# encore_Main_Board.net
KiCad netlist of a schematic drawn in EAGLE
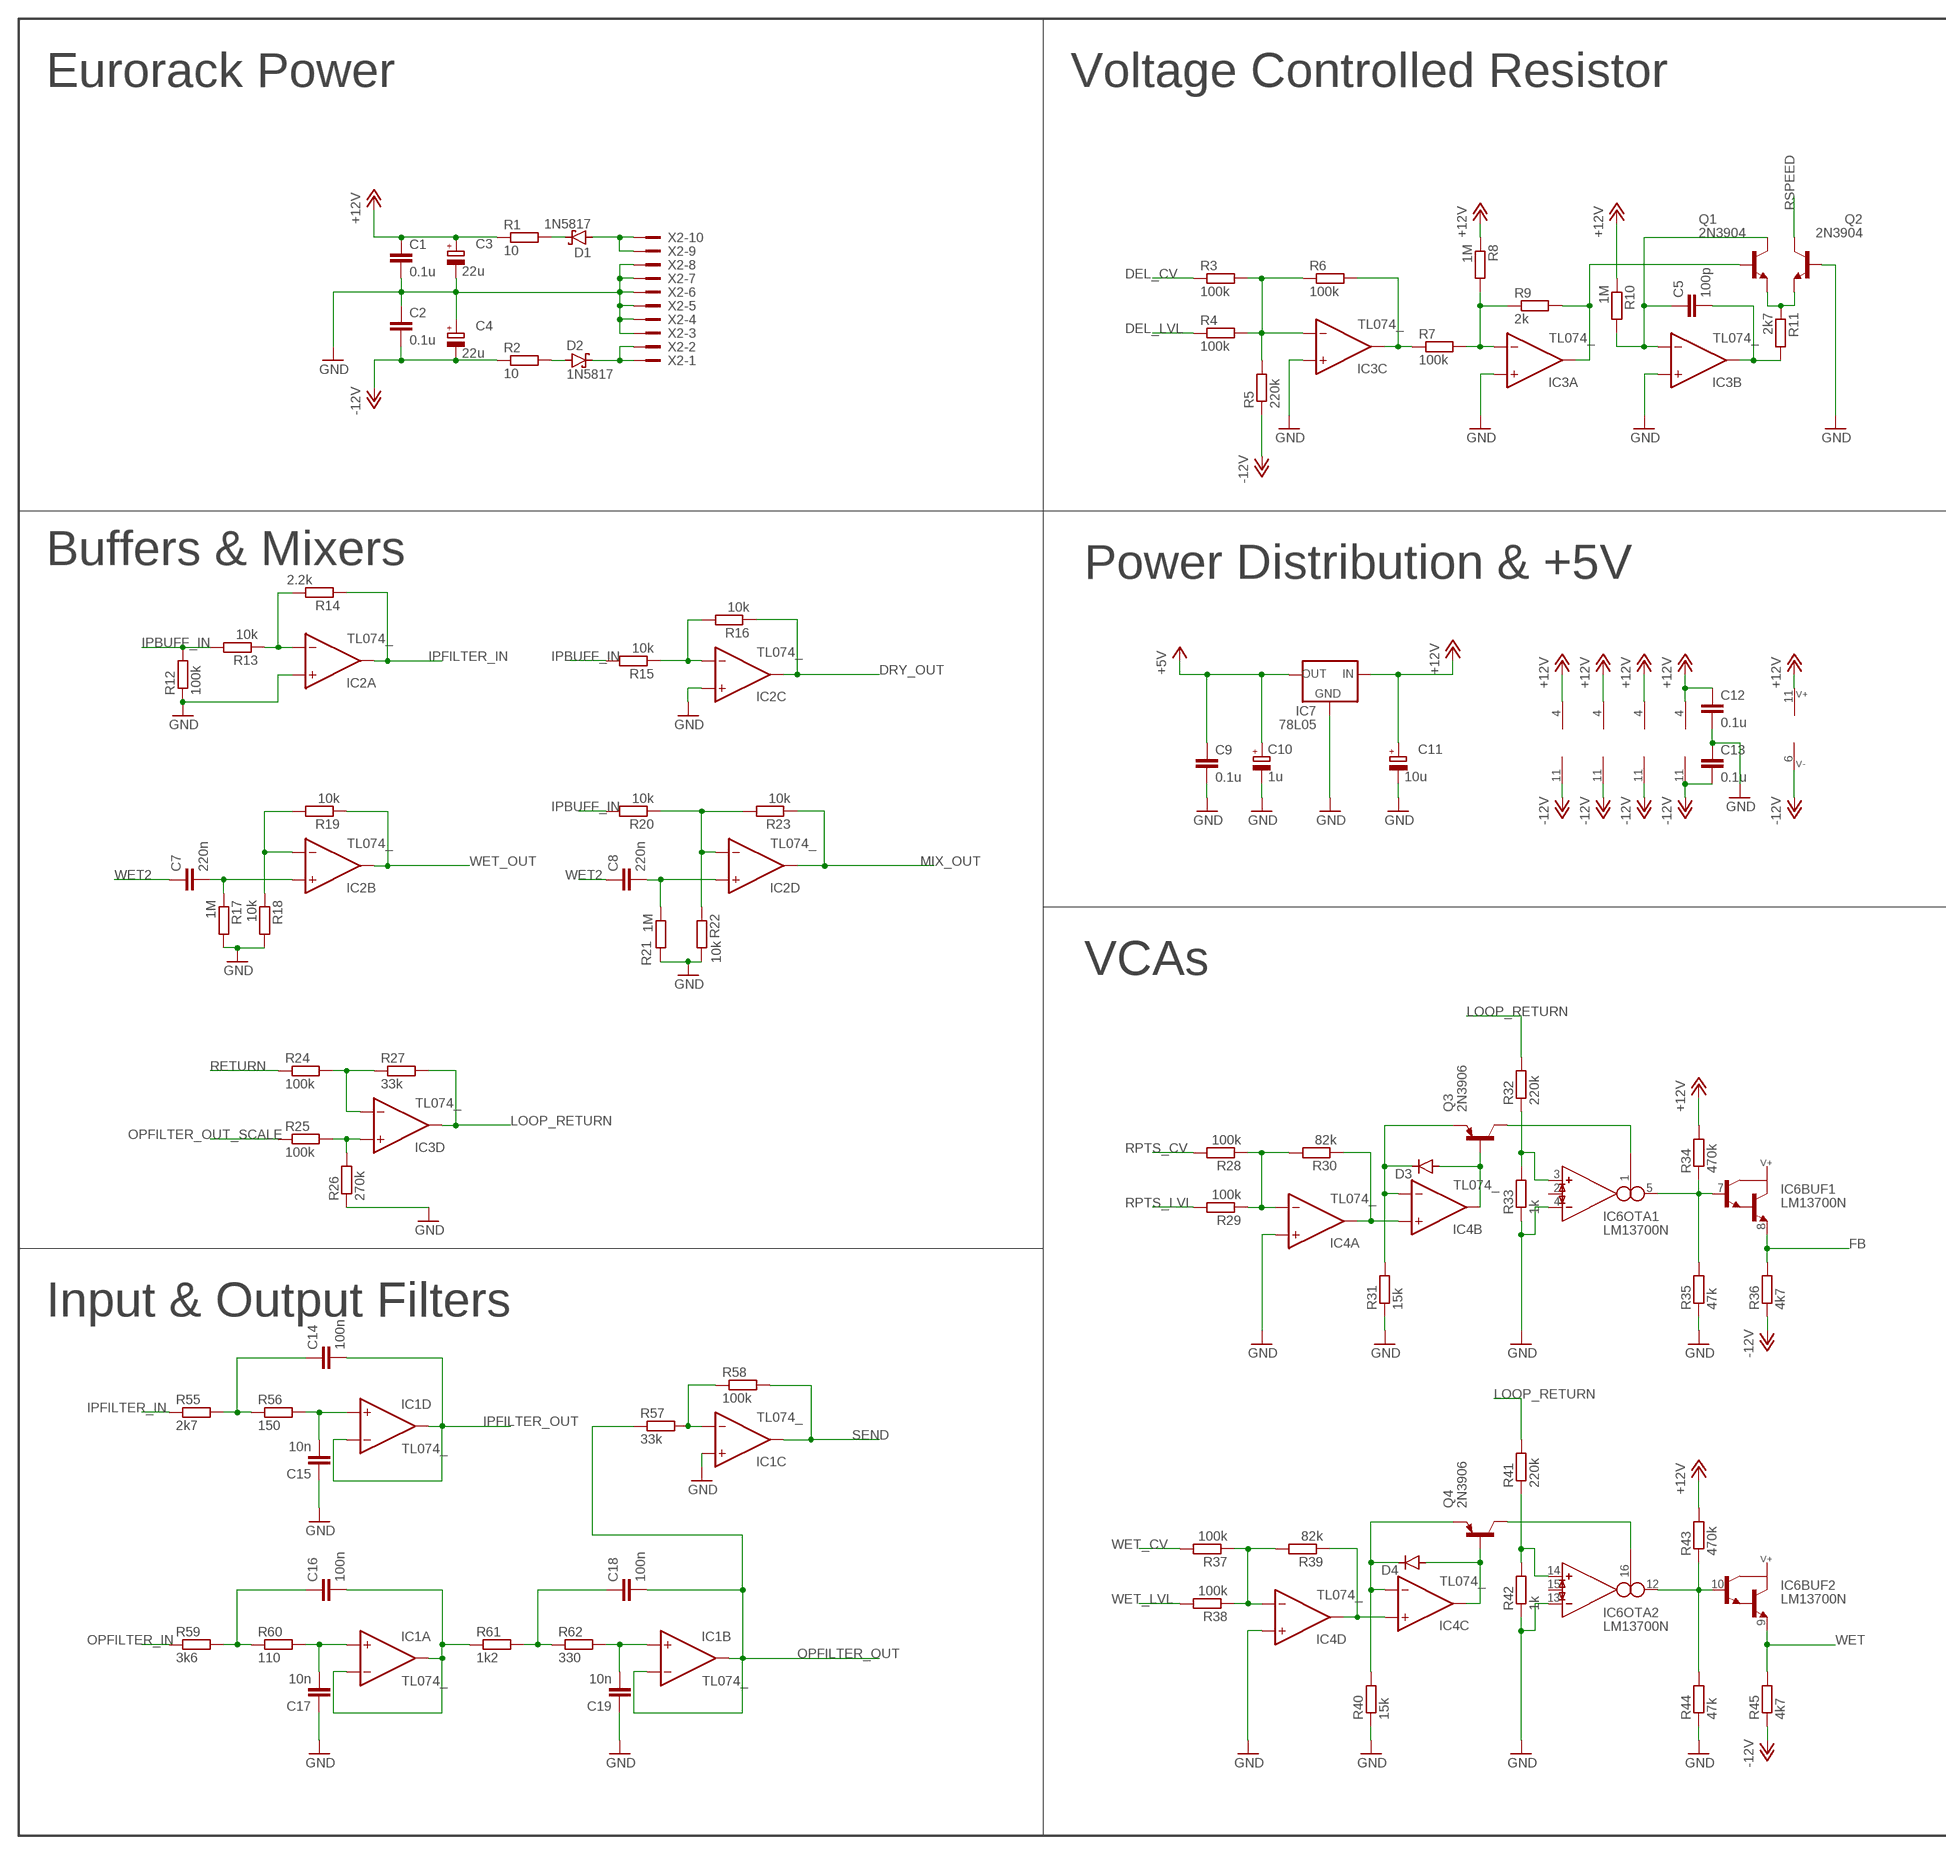
[diagram p0: schematic, sheet 1, part 1 of 2]
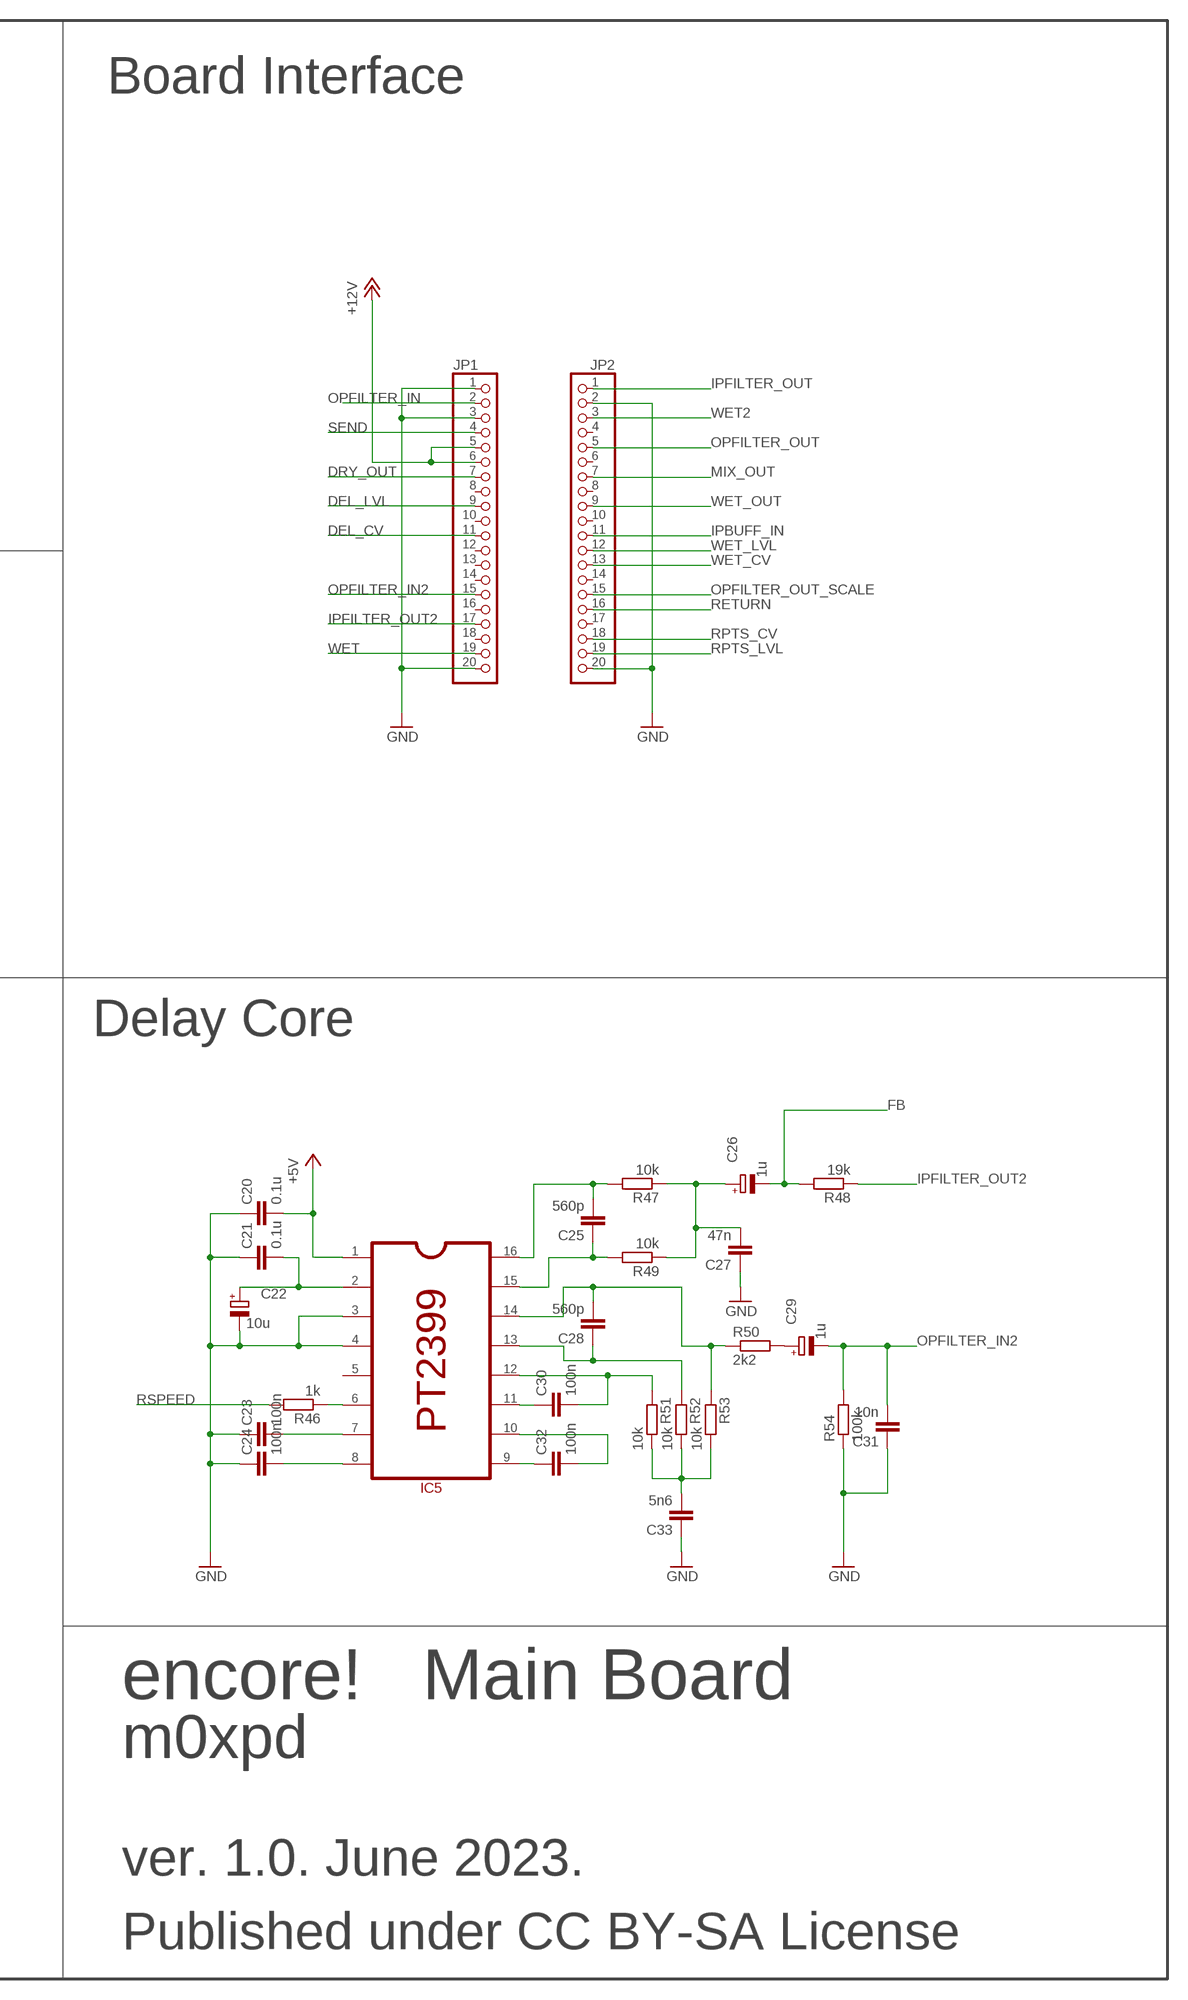
[diagram p1: schematic, sheet 1, part 2 of 2]

(export (version "E")
  (design (tool "Eeschema 10.0.6"))
  (components
    (comp (ref "C1")
      (value "0.1u")
      (footprint "eagle-import:C050-025X075")
      (libsource (lib "eagle-import") (part "C-EU050-025X075"))
    )
    (comp (ref "C2")
      (value "0.1u")
      (footprint "eagle-import:C050-025X075")
      (libsource (lib "eagle-import") (part "C-EU050-025X075"))
    )
    (comp (ref "C3")
      (value "22u")
      (footprint "eagle-import:E2,5-5")
      (libsource (lib "eagle-import") (part "CPOL-EUE2.5-5"))
    )
    (comp (ref "C4")
      (value "22u")
      (footprint "eagle-import:E2,5-5")
      (libsource (lib "eagle-import") (part "CPOL-EUE2.5-5"))
    )
    (comp (ref "C5")
      (value "100p")
      (footprint "eagle-import:C025-025X050")
      (libsource (lib "eagle-import") (part "C-EU025-025X050"))
    )
    (comp (ref "C7")
      (value "220n")
      (footprint "eagle-import:C050-024X044")
      (libsource (lib "eagle-import") (part "C-EU050-024X044"))
    )
    (comp (ref "C8")
      (value "220n")
      (footprint "eagle-import:C050-024X044")
      (libsource (lib "eagle-import") (part "C-EU050-024X044"))
    )
    (comp (ref "C9")
      (value "0.1u")
      (footprint "eagle-import:C050-025X075")
      (libsource (lib "eagle-import") (part "C-EU050-025X075"))
    )
    (comp (ref "C10")
      (value "1u")
      (footprint "eagle-import:E2,5-5")
      (libsource (lib "eagle-import") (part "CPOL-EUE2.5-5"))
    )
    (comp (ref "C11")
      (value "10u")
      (footprint "eagle-import:E2,5-5")
      (libsource (lib "eagle-import") (part "CPOL-EUE2.5-5"))
    )
    (comp (ref "C12")
      (value "0.1u")
      (footprint "eagle-import:C050-025X075")
      (libsource (lib "eagle-import") (part "C-EU050-025X075"))
    )
    (comp (ref "C13")
      (value "0.1u")
      (footprint "eagle-import:C050-025X075")
      (libsource (lib "eagle-import") (part "C-EU050-025X075"))
    )
    (comp (ref "C14")
      (value "100n")
      (footprint "eagle-import:C025-025X050")
      (libsource (lib "eagle-import") (part "C-EU025-025X050"))
    )
    (comp (ref "C15")
      (value "10n")
      (footprint "eagle-import:C025-025X050")
      (libsource (lib "eagle-import") (part "C-EU025-025X050"))
    )
    (comp (ref "C16")
      (value "100n")
      (footprint "eagle-import:C025-025X050")
      (libsource (lib "eagle-import") (part "C-EU025-025X050"))
    )
    (comp (ref "C17")
      (value "10n")
      (footprint "eagle-import:C025-025X050")
      (libsource (lib "eagle-import") (part "C-EU025-025X050"))
    )
    (comp (ref "C18")
      (value "100n")
      (footprint "eagle-import:C025-025X050")
      (libsource (lib "eagle-import") (part "C-EU025-025X050"))
    )
    (comp (ref "C19")
      (value "10n")
      (footprint "eagle-import:C025-025X050")
      (libsource (lib "eagle-import") (part "C-EU025-025X050"))
    )
    (comp (ref "C20")
      (value "0.1u")
      (footprint "eagle-import:C050-025X075")
      (libsource (lib "eagle-import") (part "C-EU050-025X075"))
    )
    (comp (ref "C21")
      (value "0.1u")
      (footprint "eagle-import:C050-025X075")
      (libsource (lib "eagle-import") (part "C-EU050-025X075"))
    )
    (comp (ref "C22")
      (value "10u")
      (footprint "eagle-import:E2,5-5")
      (libsource (lib "eagle-import") (part "CPOL-EUE2.5-5"))
    )
    (comp (ref "C23")
      (value "100n")
      (footprint "eagle-import:C050-025X075")
      (libsource (lib "eagle-import") (part "C-EU050-025X075"))
    )
    (comp (ref "C24")
      (value "100n")
      (footprint "eagle-import:C050-025X075")
      (libsource (lib "eagle-import") (part "C-EU050-025X075"))
    )
    (comp (ref "C25")
      (value "560p")
      (footprint "eagle-import:C025-025X050")
      (libsource (lib "eagle-import") (part "C-EU025-025X050"))
    )
    (comp (ref "C26")
      (value "1u")
      (footprint "eagle-import:E2,5-5")
      (libsource (lib "eagle-import") (part "CPOL-EUE2.5-5"))
    )
    (comp (ref "C27")
      (value "47n")
      (footprint "eagle-import:C050-025X075")
      (libsource (lib "eagle-import") (part "C-EU050-025X075"))
    )
    (comp (ref "C28")
      (value "560p")
      (footprint "eagle-import:C025-025X050")
      (libsource (lib "eagle-import") (part "C-EU025-025X050"))
    )
    (comp (ref "C29")
      (value "1u")
      (footprint "eagle-import:E2,5-5")
      (libsource (lib "eagle-import") (part "CPOL-EUE2.5-5"))
    )
    (comp (ref "C30")
      (value "100n")
      (footprint "eagle-import:C050-025X075")
      (libsource (lib "eagle-import") (part "C-EU050-025X075"))
    )
    (comp (ref "C31")
      (value "10n")
      (footprint "eagle-import:C025-025X050")
      (libsource (lib "eagle-import") (part "C-EU025-025X050"))
    )
    (comp (ref "C32")
      (value "100n")
      (footprint "eagle-import:C050-025X075")
      (libsource (lib "eagle-import") (part "C-EU050-025X075"))
    )
    (comp (ref "C33")
      (value "5n6")
      (footprint "eagle-import:C050-025X075")
      (libsource (lib "eagle-import") (part "C-EU050-025X075"))
    )
    (comp (ref "D1")
      (value "1N5817")
      (footprint "eagle-import:DO35-7")
      (libsource (lib "eagle-import") (part "SCHOTTKY-DIODEDO35-7"))
    )
    (comp (ref "D2")
      (value "1N5817")
      (footprint "eagle-import:DO35-7")
      (libsource (lib "eagle-import") (part "SCHOTTKY-DIODEDO35-7"))
    )
    (comp (ref "D3")
      (value "1N4148DO35-7")
      (footprint "eagle-import:DO35-7")
      (libsource (lib "eagle-import") (part "1N4148DO35-7"))
    )
    (comp (ref "D4")
      (value "1N4148DO35-7")
      (footprint "eagle-import:DO35-7")
      (libsource (lib "eagle-import") (part "1N4148DO35-7"))
    )
    (comp (ref "IC1")
      (value "TL074_")
      (footprint "eagle-import:DIL14")
      (libsource (lib "eagle-import") (part "TL074_"))
    )
    (comp (ref "IC2")
      (value "TL074_")
      (footprint "eagle-import:DIL14")
      (libsource (lib "eagle-import") (part "TL074_"))
    )
    (comp (ref "IC3")
      (value "TL074_")
      (footprint "eagle-import:DIL14")
      (libsource (lib "eagle-import") (part "TL074_"))
    )
    (comp (ref "IC4")
      (value "TL074_")
      (footprint "eagle-import:DIL14")
      (libsource (lib "eagle-import") (part "TL074_"))
    )
    (comp (ref "IC5")
      (value "PT2399")
      (footprint "eagle-import:DIP-16")
      (libsource (lib "eagle-import") (part "PT2399"))
    )
    (comp (ref "IC6")
      (value "LM13700N")
      (footprint "eagle-import:DIL16")
      (libsource (lib "eagle-import") (part "LM13700N"))
    )
    (comp (ref "IC7")
      (value "78L05")
      (footprint "eagle-import:78LXX")
      (libsource (lib "eagle-import") (part "78LXX"))
    )
    (comp (ref "JP1")
      (value "PINHD-1X20")
      (footprint "eagle-import:1X20")
      (libsource (lib "eagle-import") (part "PINHD-1X20"))
    )
    (comp (ref "JP2")
      (value "PINHD-1X20")
      (footprint "eagle-import:1X20")
      (libsource (lib "eagle-import") (part "PINHD-1X20"))
    )
    (comp (ref "Q1")
      (value "2N3904")
      (footprint "eagle-import:TO92")
      (libsource (lib "eagle-import") (part "2N3904"))
    )
    (comp (ref "Q2")
      (value "2N3904")
      (footprint "eagle-import:TO92")
      (libsource (lib "eagle-import") (part "2N3904"))
    )
    (comp (ref "Q3")
      (value "2N3906")
      (footprint "eagle-import:TO92")
      (libsource (lib "eagle-import") (part "2N3906"))
    )
    (comp (ref "Q4")
      (value "2N3906")
      (footprint "eagle-import:TO92")
      (libsource (lib "eagle-import") (part "2N3906"))
    )
    (comp (ref "R1")
      (value "10")
      (footprint "eagle-import:0204_7")
      (libsource (lib "eagle-import") (part "R-EU_0204/7"))
    )
    (comp (ref "R2")
      (value "10")
      (footprint "eagle-import:0204_7")
      (libsource (lib "eagle-import") (part "R-EU_0204/7"))
    )
    (comp (ref "R3")
      (value "100k")
      (footprint "eagle-import:0204_7")
      (libsource (lib "eagle-import") (part "R-EU_0204/7"))
    )
    (comp (ref "R4")
      (value "100k")
      (footprint "eagle-import:0204_7")
      (libsource (lib "eagle-import") (part "R-EU_0204/7"))
    )
    (comp (ref "R5")
      (value "220k")
      (footprint "eagle-import:0204_7")
      (libsource (lib "eagle-import") (part "R-EU_0204/7"))
    )
    (comp (ref "R6")
      (value "100k")
      (footprint "eagle-import:0204_7")
      (libsource (lib "eagle-import") (part "R-EU_0204/7"))
    )
    (comp (ref "R7")
      (value "100k")
      (footprint "eagle-import:0204_7")
      (libsource (lib "eagle-import") (part "R-EU_0204/7"))
    )
    (comp (ref "R8")
      (value "1M")
      (footprint "eagle-import:0204_7")
      (libsource (lib "eagle-import") (part "R-EU_0204/7"))
    )
    (comp (ref "R9")
      (value "2k")
      (footprint "eagle-import:0204_7")
      (libsource (lib "eagle-import") (part "R-EU_0204/7"))
    )
    (comp (ref "R10")
      (value "1M")
      (footprint "eagle-import:0204_7")
      (libsource (lib "eagle-import") (part "R-EU_0204/7"))
    )
    (comp (ref "R11")
      (value "2k7")
      (footprint "eagle-import:0204_7")
      (libsource (lib "eagle-import") (part "R-EU_0204/7"))
    )
    (comp (ref "R12")
      (value "100k")
      (footprint "eagle-import:0204_7")
      (libsource (lib "eagle-import") (part "R-EU_0204/7"))
    )
    (comp (ref "R13")
      (value "10k")
      (footprint "eagle-import:0204_7")
      (libsource (lib "eagle-import") (part "R-EU_0204/7"))
    )
    (comp (ref "R14")
      (value "2.2k")
      (footprint "eagle-import:0204_7")
      (libsource (lib "eagle-import") (part "R-EU_0204/7"))
    )
    (comp (ref "R15")
      (value "10k")
      (footprint "eagle-import:0204_7")
      (libsource (lib "eagle-import") (part "R-EU_0204/7"))
    )
    (comp (ref "R16")
      (value "10k")
      (footprint "eagle-import:0204_7")
      (libsource (lib "eagle-import") (part "R-EU_0204/7"))
    )
    (comp (ref "R17")
      (value "1M")
      (footprint "eagle-import:0204_7")
      (libsource (lib "eagle-import") (part "R-EU_0204/7"))
    )
    (comp (ref "R18")
      (value "10k")
      (footprint "eagle-import:0204_7")
      (libsource (lib "eagle-import") (part "R-EU_0204/7"))
    )
    (comp (ref "R19")
      (value "10k")
      (footprint "eagle-import:0204_7")
      (libsource (lib "eagle-import") (part "R-EU_0204/7"))
    )
    (comp (ref "R20")
      (value "10k")
      (footprint "eagle-import:0204_7")
      (libsource (lib "eagle-import") (part "R-EU_0204/7"))
    )
    (comp (ref "R21")
      (value "1M")
      (footprint "eagle-import:0204_7")
      (libsource (lib "eagle-import") (part "R-EU_0204/7"))
    )
    (comp (ref "R22")
      (value "10k")
      (footprint "eagle-import:0204_7")
      (libsource (lib "eagle-import") (part "R-EU_0204/7"))
    )
    (comp (ref "R23")
      (value "10k")
      (footprint "eagle-import:0204_7")
      (libsource (lib "eagle-import") (part "R-EU_0204/7"))
    )
    (comp (ref "R24")
      (value "100k")
      (footprint "eagle-import:0204_7")
      (libsource (lib "eagle-import") (part "R-EU_0204/7"))
    )
    (comp (ref "R25")
      (value "100k")
      (footprint "eagle-import:0204_7")
      (libsource (lib "eagle-import") (part "R-EU_0204/7"))
    )
    (comp (ref "R26")
      (value "270k")
      (footprint "eagle-import:0204_7")
      (libsource (lib "eagle-import") (part "R-EU_0204/7"))
    )
    (comp (ref "R27")
      (value "33k")
      (footprint "eagle-import:0204_7")
      (libsource (lib "eagle-import") (part "R-EU_0204/7"))
    )
    (comp (ref "R28")
      (value "100k")
      (footprint "eagle-import:0204_7")
      (libsource (lib "eagle-import") (part "R-EU_0204/7"))
    )
    (comp (ref "R29")
      (value "100k")
      (footprint "eagle-import:0204_7")
      (libsource (lib "eagle-import") (part "R-EU_0204/7"))
    )
    (comp (ref "R30")
      (value "82k")
      (footprint "eagle-import:0204_7")
      (libsource (lib "eagle-import") (part "R-EU_0204/7"))
    )
    (comp (ref "R31")
      (value "15k")
      (footprint "eagle-import:0204_7")
      (libsource (lib "eagle-import") (part "R-EU_0204/7"))
    )
    (comp (ref "R32")
      (value "220k")
      (footprint "eagle-import:0204_7")
      (libsource (lib "eagle-import") (part "R-EU_0204/7"))
    )
    (comp (ref "R33")
      (value "1k")
      (footprint "eagle-import:0204_7")
      (libsource (lib "eagle-import") (part "R-EU_0204/7"))
    )
    (comp (ref "R34")
      (value "470k")
      (footprint "eagle-import:0204_7")
      (libsource (lib "eagle-import") (part "R-EU_0204/7"))
    )
    (comp (ref "R35")
      (value "47k")
      (footprint "eagle-import:0204_7")
      (libsource (lib "eagle-import") (part "R-EU_0204/7"))
    )
    (comp (ref "R36")
      (value "4k7")
      (footprint "eagle-import:0204_7")
      (libsource (lib "eagle-import") (part "R-EU_0204/7"))
    )
    (comp (ref "R37")
      (value "100k")
      (footprint "eagle-import:0204_7")
      (libsource (lib "eagle-import") (part "R-EU_0204/7"))
    )
    (comp (ref "R38")
      (value "100k")
      (footprint "eagle-import:0204_7")
      (libsource (lib "eagle-import") (part "R-EU_0204/7"))
    )
    (comp (ref "R39")
      (value "82k")
      (footprint "eagle-import:0204_7")
      (libsource (lib "eagle-import") (part "R-EU_0204/7"))
    )
    (comp (ref "R40")
      (value "15k")
      (footprint "eagle-import:0204_7")
      (libsource (lib "eagle-import") (part "R-EU_0204/7"))
    )
    (comp (ref "R41")
      (value "220k")
      (footprint "eagle-import:0204_7")
      (libsource (lib "eagle-import") (part "R-EU_0204/7"))
    )
    (comp (ref "R42")
      (value "1k")
      (footprint "eagle-import:0204_7")
      (libsource (lib "eagle-import") (part "R-EU_0204/7"))
    )
    (comp (ref "R43")
      (value "470k")
      (footprint "eagle-import:0204_7")
      (libsource (lib "eagle-import") (part "R-EU_0204/7"))
    )
    (comp (ref "R44")
      (value "47k")
      (footprint "eagle-import:0204_7")
      (libsource (lib "eagle-import") (part "R-EU_0204/7"))
    )
    (comp (ref "R45")
      (value "4k7")
      (footprint "eagle-import:0204_7")
      (libsource (lib "eagle-import") (part "R-EU_0204/7"))
    )
    (comp (ref "R46")
      (value "1k")
      (footprint "eagle-import:0204_7")
      (libsource (lib "eagle-import") (part "R-EU_0204/7"))
    )
    (comp (ref "R47")
      (value "10k")
      (footprint "eagle-import:0204_7")
      (libsource (lib "eagle-import") (part "R-EU_0204/7"))
    )
    (comp (ref "R48")
      (value "19k")
      (footprint "eagle-import:0204_7")
      (libsource (lib "eagle-import") (part "R-EU_0204/7"))
    )
    (comp (ref "R49")
      (value "10k")
      (footprint "eagle-import:0204_7")
      (libsource (lib "eagle-import") (part "R-EU_0204/7"))
    )
    (comp (ref "R50")
      (value "2k2")
      (footprint "eagle-import:0204_7")
      (libsource (lib "eagle-import") (part "R-EU_0204/7"))
    )
    (comp (ref "R51")
      (value "10k")
      (footprint "eagle-import:0204_7")
      (libsource (lib "eagle-import") (part "R-EU_0204/7"))
    )
    (comp (ref "R52")
      (value "10k")
      (footprint "eagle-import:0204_7")
      (libsource (lib "eagle-import") (part "R-EU_0204/7"))
    )
    (comp (ref "R53")
      (value "10k")
      (footprint "eagle-import:0204_7")
      (libsource (lib "eagle-import") (part "R-EU_0204/7"))
    )
    (comp (ref "R54")
      (value "100k")
      (footprint "eagle-import:0204_7")
      (libsource (lib "eagle-import") (part "R-EU_0204/7"))
    )
    (comp (ref "R55")
      (value "2k7")
      (footprint "eagle-import:0204_7")
      (libsource (lib "eagle-import") (part "R-EU_0204/7"))
    )
    (comp (ref "R56")
      (value "150")
      (footprint "eagle-import:0204_7")
      (libsource (lib "eagle-import") (part "R-EU_0204/7"))
    )
    (comp (ref "R57")
      (value "33k")
      (footprint "eagle-import:0204_7")
      (libsource (lib "eagle-import") (part "R-EU_0204/7"))
    )
    (comp (ref "R58")
      (value "100k")
      (footprint "eagle-import:0204_7")
      (libsource (lib "eagle-import") (part "R-EU_0204/7"))
    )
    (comp (ref "R59")
      (value "3k6")
      (footprint "eagle-import:0204_7")
      (libsource (lib "eagle-import") (part "R-EU_0204/7"))
    )
    (comp (ref "R60")
      (value "110")
      (footprint "eagle-import:0204_7")
      (libsource (lib "eagle-import") (part "R-EU_0204/7"))
    )
    (comp (ref "R61")
      (value "1k2")
      (footprint "eagle-import:0204_7")
      (libsource (lib "eagle-import") (part "R-EU_0204/7"))
    )
    (comp (ref "R62")
      (value "330")
      (footprint "eagle-import:0204_7")
      (libsource (lib "eagle-import") (part "R-EU_0204/7"))
    )
    (comp (ref "X2")
      (value "2510-")
      (footprint "eagle-import:PAK100_2500-10")
      (fields (field (name "MF") "3M") (field (name "MPN") "2510-6002UB"))
      (libsource (lib "eagle-import") (part "2510-"))
    )
  )
  (nets
    (net (code "1") (name "+5V") (class "Default")
      (node (ref "C10") (pin "+") (pinfunction "+_+") (pintype "passive"))
      (node (ref "C20") (pin "2") (pinfunction "2_2") (pintype "passive"))
      (node (ref "C9") (pin "1") (pinfunction "1_1") (pintype "passive"))
      (node (ref "IC5") (pin "1") (pinfunction "1_1") (pintype "bidirectional"))
      (node (ref "IC7") (pin "OUT") (pinfunction "OUT_OUT") (pintype "passive"))
    )
    (net (code "2") (name "+12V") (class "Default")
      (node (ref "C1") (pin "1") (pinfunction "1_1") (pintype "passive"))
      (node (ref "C11") (pin "+") (pinfunction "+_+") (pintype "passive"))
      (node (ref "C12") (pin "1") (pinfunction "1_1") (pintype "passive"))
      (node (ref "C3") (pin "+") (pinfunction "+_+") (pintype "passive"))
      (node (ref "IC1") (pin "4") (pinfunction "V+_4") (pintype "power_in"))
      (node (ref "IC2") (pin "4") (pinfunction "V+_4") (pintype "power_in"))
      (node (ref "IC3") (pin "4") (pinfunction "V+_4") (pintype "power_in"))
      (node (ref "IC4") (pin "4") (pinfunction "V+_4") (pintype "power_in"))
      (node (ref "IC6") (pin "11") (pinfunction "V+_11") (pintype "power_in"))
      (node (ref "IC7") (pin "IN") (pinfunction "IN_IN") (pintype "input"))
      (node (ref "JP1") (pin "5") (pinfunction "5_5") (pintype "passive"))
      (node (ref "JP1") (pin "6") (pinfunction "6_6") (pintype "passive"))
      (node (ref "R1") (pin "1") (pinfunction "1_1") (pintype "passive"))
      (node (ref "R10") (pin "1") (pinfunction "1_1") (pintype "passive"))
      (node (ref "R34") (pin "2") (pinfunction "2_2") (pintype "passive"))
      (node (ref "R43") (pin "2") (pinfunction "2_2") (pintype "passive"))
      (node (ref "R8") (pin "1") (pinfunction "1_1") (pintype "passive"))
    )
    (net (code "3") (name "-12V") (class "Default")
      (node (ref "C13") (pin "2") (pinfunction "2_2") (pintype "passive"))
      (node (ref "C2") (pin "2") (pinfunction "2_2") (pintype "passive"))
      (node (ref "C4") (pin "-") (pinfunction "-_-") (pintype "passive"))
      (node (ref "IC1") (pin "11") (pinfunction "V-_11") (pintype "power_in"))
      (node (ref "IC2") (pin "11") (pinfunction "V-_11") (pintype "power_in"))
      (node (ref "IC3") (pin "11") (pinfunction "V-_11") (pintype "power_in"))
      (node (ref "IC4") (pin "11") (pinfunction "V-_11") (pintype "power_in"))
      (node (ref "IC6") (pin "6") (pinfunction "V-_6") (pintype "power_in"))
      (node (ref "R2") (pin "1") (pinfunction "1_1") (pintype "passive"))
      (node (ref "R36") (pin "1") (pinfunction "1_1") (pintype "passive"))
      (node (ref "R45") (pin "1") (pinfunction "1_1") (pintype "passive"))
      (node (ref "R5") (pin "1") (pinfunction "1_1") (pintype "passive"))
    )
    (net (code "4") (name "/DEL_CV") (class "Default")
      (node (ref "JP1") (pin "11") (pinfunction "11_11") (pintype "passive"))
      (node (ref "R3") (pin "1") (pinfunction "1_1") (pintype "passive"))
    )
    (net (code "5") (name "/DEL_LVL") (class "Default")
      (node (ref "JP1") (pin "9") (pinfunction "9_9") (pintype "passive"))
      (node (ref "R4") (pin "1") (pinfunction "1_1") (pintype "passive"))
    )
    (net (code "6") (name "/DRY_OUT") (class "Default")
      (node (ref "IC2") (pin "8") (pinfunction "OUT_8") (pintype "output"))
      (node (ref "JP1") (pin "7") (pinfunction "7_7") (pintype "passive"))
      (node (ref "R16") (pin "1") (pinfunction "1_1") (pintype "passive"))
    )
    (net (code "7") (name "/FB") (class "Default")
      (node (ref "C26") (pin "-") (pinfunction "-_-") (pintype "passive"))
      (node (ref "IC6") (pin "8") (pinfunction "E_8") (pintype "passive"))
      (node (ref "R36") (pin "2") (pinfunction "2_2") (pintype "passive"))
      (node (ref "R48") (pin "2") (pinfunction "2_2") (pintype "passive"))
    )
    (net (code "8") (name "/IPBUFF_IN") (class "Default")
      (node (ref "JP2") (pin "11") (pinfunction "11_11") (pintype "passive"))
      (node (ref "R12") (pin "2") (pinfunction "2_2") (pintype "passive"))
      (node (ref "R13") (pin "2") (pinfunction "2_2") (pintype "passive"))
      (node (ref "R15") (pin "2") (pinfunction "2_2") (pintype "passive"))
      (node (ref "R20") (pin "2") (pinfunction "2_2") (pintype "passive"))
    )
    (net (code "9") (name "/IPFILTER_IN") (class "Default")
      (node (ref "IC2") (pin "1") (pinfunction "OUT_1") (pintype "output"))
      (node (ref "R14") (pin "1") (pinfunction "1_1") (pintype "passive"))
      (node (ref "R55") (pin "1") (pinfunction "1_1") (pintype "passive"))
    )
    (net (code "10") (name "/IPFILTER_OUT") (class "Default")
      (node (ref "C14") (pin "2") (pinfunction "2_2") (pintype "passive"))
      (node (ref "IC1") (pin "13") (pinfunction "-IN_13") (pintype "input"))
      (node (ref "IC1") (pin "14") (pinfunction "OUT_14") (pintype "output"))
      (node (ref "JP2") (pin "1") (pinfunction "1_1") (pintype "passive"))
    )
    (net (code "11") (name "/IPFILTER_OUT2") (class "Default")
      (node (ref "JP1") (pin "17") (pinfunction "17_17") (pintype "passive"))
      (node (ref "R48") (pin "1") (pinfunction "1_1") (pintype "passive"))
    )
    (net (code "12") (name "/LOOP_RETURN") (class "Default")
      (node (ref "IC3") (pin "14") (pinfunction "OUT_14") (pintype "output"))
      (node (ref "R27") (pin "2") (pinfunction "2_2") (pintype "passive"))
      (node (ref "R32") (pin "2") (pinfunction "2_2") (pintype "passive"))
      (node (ref "R41") (pin "2") (pinfunction "2_2") (pintype "passive"))
    )
    (net (code "13") (name "/MIX_OUT") (class "Default")
      (node (ref "IC2") (pin "14") (pinfunction "OUT_14") (pintype "output"))
      (node (ref "JP2") (pin "7") (pinfunction "7_7") (pintype "passive"))
      (node (ref "R23") (pin "1") (pinfunction "1_1") (pintype "passive"))
    )
    (net (code "14") (name "/OPFILTER_IN") (class "Default")
      (node (ref "JP1") (pin "2") (pinfunction "2_2") (pintype "passive"))
      (node (ref "R59") (pin "1") (pinfunction "1_1") (pintype "passive"))
    )
    (net (code "15") (name "/OPFILTER_IN2") (class "Default")
      (node (ref "C29") (pin "-") (pinfunction "-_-") (pintype "passive"))
      (node (ref "C31") (pin "2") (pinfunction "2_2") (pintype "passive"))
      (node (ref "JP1") (pin "15") (pinfunction "15_15") (pintype "passive"))
      (node (ref "R54") (pin "2") (pinfunction "2_2") (pintype "passive"))
    )
    (net (code "16") (name "/OPFILTER_OUT") (class "Default")
      (node (ref "C18") (pin "2") (pinfunction "2_2") (pintype "passive"))
      (node (ref "IC1") (pin "6") (pinfunction "-IN_6") (pintype "input"))
      (node (ref "IC1") (pin "7") (pinfunction "OUT_7") (pintype "output"))
      (node (ref "JP2") (pin "5") (pinfunction "5_5") (pintype "passive"))
      (node (ref "R57") (pin "1") (pinfunction "1_1") (pintype "passive"))
    )
    (net (code "17") (name "/OPFILTER_OUT_SCALE") (class "Default")
      (node (ref "JP2") (pin "15") (pinfunction "15_15") (pintype "passive"))
      (node (ref "R25") (pin "1") (pinfunction "1_1") (pintype "passive"))
    )
    (net (code "18") (name "/RETURN") (class "Default")
      (node (ref "JP2") (pin "16") (pinfunction "16_16") (pintype "passive"))
      (node (ref "R24") (pin "1") (pinfunction "1_1") (pintype "passive"))
    )
    (net (code "19") (name "/RPTS_CV") (class "Default")
      (node (ref "JP2") (pin "18") (pinfunction "18_18") (pintype "passive"))
      (node (ref "R28") (pin "2") (pinfunction "2_2") (pintype "passive"))
    )
    (net (code "20") (name "/RPTS_LVL") (class "Default")
      (node (ref "JP2") (pin "19") (pinfunction "19_19") (pintype "passive"))
      (node (ref "R29") (pin "2") (pinfunction "2_2") (pintype "passive"))
    )
    (net (code "21") (name "/RSPEED") (class "Default")
      (node (ref "Q2") (pin "1") (pinfunction "C_1") (pintype "passive"))
      (node (ref "R46") (pin "2") (pinfunction "2_2") (pintype "passive"))
    )
    (net (code "22") (name "/SEND") (class "Default")
      (node (ref "IC1") (pin "8") (pinfunction "OUT_8") (pintype "output"))
      (node (ref "JP1") (pin "4") (pinfunction "4_4") (pintype "passive"))
      (node (ref "R58") (pin "2") (pinfunction "2_2") (pintype "passive"))
    )
    (net (code "23") (name "/WET") (class "Default")
      (node (ref "IC6") (pin "9") (pinfunction "E_9") (pintype "passive"))
      (node (ref "JP1") (pin "19") (pinfunction "19_19") (pintype "passive"))
      (node (ref "R45") (pin "2") (pinfunction "2_2") (pintype "passive"))
    )
    (net (code "24") (name "/WET2") (class "Default")
      (node (ref "C7") (pin "1") (pinfunction "1_1") (pintype "passive"))
      (node (ref "C8") (pin "1") (pinfunction "1_1") (pintype "passive"))
      (node (ref "JP2") (pin "3") (pinfunction "3_3") (pintype "passive"))
    )
    (net (code "25") (name "/WET_CV") (class "Default")
      (node (ref "JP2") (pin "13") (pinfunction "13_13") (pintype "passive"))
      (node (ref "R37") (pin "2") (pinfunction "2_2") (pintype "passive"))
    )
    (net (code "26") (name "/WET_LVL") (class "Default")
      (node (ref "JP2") (pin "12") (pinfunction "12_12") (pintype "passive"))
      (node (ref "R38") (pin "2") (pinfunction "2_2") (pintype "passive"))
    )
    (net (code "27") (name "/WET_OUT") (class "Default")
      (node (ref "IC2") (pin "7") (pinfunction "OUT_7") (pintype "output"))
      (node (ref "JP2") (pin "9") (pinfunction "9_9") (pintype "passive"))
      (node (ref "R19") (pin "1") (pinfunction "1_1") (pintype "passive"))
    )
    (net (code "28") (name "GND") (class "Default")
      (node (ref "C1") (pin "2") (pinfunction "2_2") (pintype "passive"))
      (node (ref "C10") (pin "-") (pinfunction "-_-") (pintype "passive"))
      (node (ref "C11") (pin "-") (pinfunction "-_-") (pintype "passive"))
      (node (ref "C12") (pin "2") (pinfunction "2_2") (pintype "passive"))
      (node (ref "C13") (pin "1") (pinfunction "1_1") (pintype "passive"))
      (node (ref "C15") (pin "1") (pinfunction "1_1") (pintype "passive"))
      (node (ref "C17") (pin "1") (pinfunction "1_1") (pintype "passive"))
      (node (ref "C19") (pin "1") (pinfunction "1_1") (pintype "passive"))
      (node (ref "C2") (pin "1") (pinfunction "1_1") (pintype "passive"))
      (node (ref "C20") (pin "1") (pinfunction "1_1") (pintype "passive"))
      (node (ref "C21") (pin "1") (pinfunction "1_1") (pintype "passive"))
      (node (ref "C22") (pin "-") (pinfunction "-_-") (pintype "passive"))
      (node (ref "C23") (pin "1") (pinfunction "1_1") (pintype "passive"))
      (node (ref "C24") (pin "1") (pinfunction "1_1") (pintype "passive"))
      (node (ref "C27") (pin "1") (pinfunction "1_1") (pintype "passive"))
      (node (ref "C3") (pin "-") (pinfunction "-_-") (pintype "passive"))
      (node (ref "C31") (pin "1") (pinfunction "1_1") (pintype "passive"))
      (node (ref "C33") (pin "1") (pinfunction "1_1") (pintype "passive"))
      (node (ref "C4") (pin "+") (pinfunction "+_+") (pintype "passive"))
      (node (ref "C9") (pin "2") (pinfunction "2_2") (pintype "passive"))
      (node (ref "IC1") (pin "10") (pinfunction "+IN_10") (pintype "input"))
      (node (ref "IC2") (pin "10") (pinfunction "+IN_10") (pintype "input"))
      (node (ref "IC2") (pin "3") (pinfunction "+IN_3") (pintype "input"))
      (node (ref "IC3") (pin "10") (pinfunction "+IN_10") (pintype "input"))
      (node (ref "IC3") (pin "3") (pinfunction "+IN_3") (pintype "input"))
      (node (ref "IC3") (pin "5") (pinfunction "+IN_5") (pintype "input"))
      (node (ref "IC4") (pin "12") (pinfunction "+IN_12") (pintype "input"))
      (node (ref "IC4") (pin "3") (pinfunction "+IN_3") (pintype "input"))
      (node (ref "IC5") (pin "3") (pinfunction "3_3") (pintype "bidirectional"))
      (node (ref "IC5") (pin "4") (pinfunction "4_4") (pintype "bidirectional"))
      (node (ref "IC6") (pin "13") (pinfunction "IN_N_13") (pintype "input"))
      (node (ref "IC6") (pin "4") (pinfunction "IN_N_4") (pintype "input"))
      (node (ref "IC7") (pin "GND") (pinfunction "GND_GND") (pintype "input"))
      (node (ref "JP1") (pin "1") (pinfunction "1_1") (pintype "passive"))
      (node (ref "JP1") (pin "20") (pinfunction "20_20") (pintype "passive"))
      (node (ref "JP1") (pin "3") (pinfunction "3_3") (pintype "passive"))
      (node (ref "JP2") (pin "2") (pinfunction "2_2") (pintype "passive"))
      (node (ref "JP2") (pin "20") (pinfunction "20_20") (pintype "passive"))
      (node (ref "Q2") (pin "2") (pinfunction "B_2") (pintype "passive"))
      (node (ref "R12") (pin "1") (pinfunction "1_1") (pintype "passive"))
      (node (ref "R17") (pin "2") (pinfunction "2_2") (pintype "passive"))
      (node (ref "R18") (pin "2") (pinfunction "2_2") (pintype "passive"))
      (node (ref "R21") (pin "2") (pinfunction "2_2") (pintype "passive"))
      (node (ref "R22") (pin "2") (pinfunction "2_2") (pintype "passive"))
      (node (ref "R26") (pin "1") (pinfunction "1_1") (pintype "passive"))
      (node (ref "R31") (pin "1") (pinfunction "1_1") (pintype "passive"))
      (node (ref "R33") (pin "1") (pinfunction "1_1") (pintype "passive"))
      (node (ref "R35") (pin "1") (pinfunction "1_1") (pintype "passive"))
      (node (ref "R40") (pin "1") (pinfunction "1_1") (pintype "passive"))
      (node (ref "R42") (pin "1") (pinfunction "1_1") (pintype "passive"))
      (node (ref "R44") (pin "1") (pinfunction "1_1") (pintype "passive"))
      (node (ref "R54") (pin "1") (pinfunction "1_1") (pintype "passive"))
      (node (ref "X2") (pin "3") (pinfunction "KL_3") (pintype "passive"))
      (node (ref "X2") (pin "4") (pinfunction "KL_4") (pintype "passive"))
      (node (ref "X2") (pin "5") (pinfunction "KL_5") (pintype "passive"))
      (node (ref "X2") (pin "6") (pinfunction "KL_6") (pintype "passive"))
      (node (ref "X2") (pin "7") (pinfunction "KL_7") (pintype "passive"))
      (node (ref "X2") (pin "8") (pinfunction "KL_8") (pintype "passive"))
    )
    (net (code "29") (name "Net-(C14-Pad1)") (class "Default")
      (node (ref "C14") (pin "1") (pinfunction "1_1") (pintype "passive"))
      (node (ref "R55") (pin "2") (pinfunction "2_2") (pintype "passive"))
      (node (ref "R56") (pin "1") (pinfunction "1_1") (pintype "passive"))
    )
    (net (code "30") (name "Net-(C16-Pad1)") (class "Default")
      (node (ref "C16") (pin "1") (pinfunction "1_1") (pintype "passive"))
      (node (ref "R59") (pin "2") (pinfunction "2_2") (pintype "passive"))
      (node (ref "R60") (pin "1") (pinfunction "1_1") (pintype "passive"))
    )
    (net (code "31") (name "Net-(C18-Pad1)") (class "Default")
      (node (ref "C18") (pin "1") (pinfunction "1_1") (pintype "passive"))
      (node (ref "R61") (pin "2") (pinfunction "2_2") (pintype "passive"))
      (node (ref "R62") (pin "1") (pinfunction "1_1") (pintype "passive"))
    )
    (net (code "32") (name "Net-(C21-Pad2)") (class "Default")
      (node (ref "C21") (pin "2") (pinfunction "2_2") (pintype "passive"))
      (node (ref "C22") (pin "+") (pinfunction "+_+") (pintype "passive"))
      (node (ref "IC5") (pin "2") (pinfunction "2_2") (pintype "bidirectional"))
    )
    (net (code "33") (name "Net-(C23-Pad2)") (class "Default")
      (node (ref "C23") (pin "2") (pinfunction "2_2") (pintype "passive"))
      (node (ref "IC5") (pin "7") (pinfunction "7_7") (pintype "bidirectional"))
    )
    (net (code "34") (name "Net-(C24-Pad2)") (class "Default")
      (node (ref "C24") (pin "2") (pinfunction "2_2") (pintype "passive"))
      (node (ref "IC5") (pin "8") (pinfunction "8_8") (pintype "bidirectional"))
    )
    (net (code "35") (name "Net-(C25-Pad1)") (class "Default")
      (node (ref "C25") (pin "1") (pinfunction "1_1") (pintype "passive"))
      (node (ref "IC5") (pin "15") (pinfunction "15_15") (pintype "bidirectional"))
      (node (ref "R49") (pin "2") (pinfunction "2_2") (pintype "passive"))
    )
    (net (code "36") (name "Net-(C25-Pad2)") (class "Default")
      (node (ref "C25") (pin "2") (pinfunction "2_2") (pintype "passive"))
      (node (ref "IC5") (pin "16") (pinfunction "16_16") (pintype "bidirectional"))
      (node (ref "R47") (pin "2") (pinfunction "2_2") (pintype "passive"))
    )
    (net (code "37") (name "Net-(C26-Pad+)") (class "Default")
      (node (ref "C26") (pin "+") (pinfunction "+_+") (pintype "passive"))
      (node (ref "C27") (pin "2") (pinfunction "2_2") (pintype "passive"))
      (node (ref "R47") (pin "1") (pinfunction "1_1") (pintype "passive"))
      (node (ref "R49") (pin "1") (pinfunction "1_1") (pintype "passive"))
    )
    (net (code "38") (name "Net-(C28-Pad1)") (class "Default")
      (node (ref "C28") (pin "1") (pinfunction "1_1") (pintype "passive"))
      (node (ref "IC5") (pin "13") (pinfunction "13_13") (pintype "bidirectional"))
      (node (ref "R52") (pin "1") (pinfunction "1_1") (pintype "passive"))
    )
    (net (code "39") (name "Net-(C28-Pad2)") (class "Default")
      (node (ref "C28") (pin "2") (pinfunction "2_2") (pintype "passive"))
      (node (ref "IC5") (pin "14") (pinfunction "14_14") (pintype "bidirectional"))
      (node (ref "R50") (pin "1") (pinfunction "1_1") (pintype "passive"))
      (node (ref "R53") (pin "1") (pinfunction "1_1") (pintype "passive"))
    )
    (net (code "40") (name "Net-(C29-Pad+)") (class "Default")
      (node (ref "C29") (pin "+") (pinfunction "+_+") (pintype "passive"))
      (node (ref "R50") (pin "2") (pinfunction "2_2") (pintype "passive"))
    )
    (net (code "41") (name "Net-(C30-Pad1)") (class "Default")
      (node (ref "C30") (pin "1") (pinfunction "1_1") (pintype "passive"))
      (node (ref "IC5") (pin "11") (pinfunction "11_11") (pintype "bidirectional"))
    )
    (net (code "42") (name "Net-(C30-Pad2)") (class "Default")
      (node (ref "C30") (pin "2") (pinfunction "2_2") (pintype "passive"))
      (node (ref "IC5") (pin "12") (pinfunction "12_12") (pintype "bidirectional"))
      (node (ref "R51") (pin "1") (pinfunction "1_1") (pintype "passive"))
    )
    (net (code "43") (name "Net-(C32-Pad1)") (class "Default")
      (node (ref "C32") (pin "1") (pinfunction "1_1") (pintype "passive"))
      (node (ref "IC5") (pin "9") (pinfunction "9_9") (pintype "bidirectional"))
    )
    (net (code "44") (name "Net-(C32-Pad2)") (class "Default")
      (node (ref "C32") (pin "2") (pinfunction "2_2") (pintype "passive"))
      (node (ref "IC5") (pin "10") (pinfunction "10_10") (pintype "bidirectional"))
    )
    (net (code "45") (name "Net-(C33-Pad2)") (class "Default")
      (node (ref "C33") (pin "2") (pinfunction "2_2") (pintype "passive"))
      (node (ref "R51") (pin "2") (pinfunction "2_2") (pintype "passive"))
      (node (ref "R52") (pin "2") (pinfunction "2_2") (pintype "passive"))
      (node (ref "R53") (pin "2") (pinfunction "2_2") (pintype "passive"))
    )
    (net (code "46") (name "Net-(D1-PadC)") (class "Default")
      (node (ref "D1") (pin "C") (pinfunction "C_C") (pintype "passive"))
      (node (ref "R1") (pin "2") (pinfunction "2_2") (pintype "passive"))
    )
    (net (code "47") (name "Net-(D2-PadA)") (class "Default")
      (node (ref "D2") (pin "A") (pinfunction "A_A") (pintype "passive"))
      (node (ref "R2") (pin "2") (pinfunction "2_2") (pintype "passive"))
    )
    (net (code "48") (name "Net-(IC1A-+IN)") (class "Default")
      (node (ref "C17") (pin "2") (pinfunction "2_2") (pintype "passive"))
      (node (ref "IC1") (pin "3") (pinfunction "+IN_3") (pintype "input"))
      (node (ref "R60") (pin "2") (pinfunction "2_2") (pintype "passive"))
    )
    (net (code "49") (name "Net-(IC1A--IN)") (class "Default")
      (node (ref "C16") (pin "2") (pinfunction "2_2") (pintype "passive"))
      (node (ref "IC1") (pin "1") (pinfunction "OUT_1") (pintype "output"))
      (node (ref "IC1") (pin "2") (pinfunction "-IN_2") (pintype "input"))
      (node (ref "R61") (pin "1") (pinfunction "1_1") (pintype "passive"))
    )
    (net (code "50") (name "Net-(IC1B-+IN)") (class "Default")
      (node (ref "C19") (pin "2") (pinfunction "2_2") (pintype "passive"))
      (node (ref "IC1") (pin "5") (pinfunction "+IN_5") (pintype "input"))
      (node (ref "R62") (pin "2") (pinfunction "2_2") (pintype "passive"))
    )
    (net (code "51") (name "Net-(IC1C--IN)") (class "Default")
      (node (ref "IC1") (pin "9") (pinfunction "-IN_9") (pintype "input"))
      (node (ref "R57") (pin "2") (pinfunction "2_2") (pintype "passive"))
      (node (ref "R58") (pin "1") (pinfunction "1_1") (pintype "passive"))
    )
    (net (code "52") (name "Net-(IC1D-+IN)") (class "Default")
      (node (ref "C15") (pin "2") (pinfunction "2_2") (pintype "passive"))
      (node (ref "IC1") (pin "12") (pinfunction "+IN_12") (pintype "input"))
      (node (ref "R56") (pin "2") (pinfunction "2_2") (pintype "passive"))
    )
    (net (code "53") (name "Net-(IC2A--IN)") (class "Default")
      (node (ref "IC2") (pin "2") (pinfunction "-IN_2") (pintype "input"))
      (node (ref "R13") (pin "1") (pinfunction "1_1") (pintype "passive"))
      (node (ref "R14") (pin "2") (pinfunction "2_2") (pintype "passive"))
    )
    (net (code "54") (name "Net-(IC2B-+IN)") (class "Default")
      (node (ref "C7") (pin "2") (pinfunction "2_2") (pintype "passive"))
      (node (ref "IC2") (pin "5") (pinfunction "+IN_5") (pintype "input"))
      (node (ref "R17") (pin "1") (pinfunction "1_1") (pintype "passive"))
    )
    (net (code "55") (name "Net-(IC2B--IN)") (class "Default")
      (node (ref "IC2") (pin "6") (pinfunction "-IN_6") (pintype "input"))
      (node (ref "R18") (pin "1") (pinfunction "1_1") (pintype "passive"))
      (node (ref "R19") (pin "2") (pinfunction "2_2") (pintype "passive"))
    )
    (net (code "56") (name "Net-(IC2C--IN)") (class "Default")
      (node (ref "IC2") (pin "9") (pinfunction "-IN_9") (pintype "input"))
      (node (ref "R15") (pin "1") (pinfunction "1_1") (pintype "passive"))
      (node (ref "R16") (pin "2") (pinfunction "2_2") (pintype "passive"))
    )
    (net (code "57") (name "Net-(IC2D-+IN)") (class "Default")
      (node (ref "C8") (pin "2") (pinfunction "2_2") (pintype "passive"))
      (node (ref "IC2") (pin "12") (pinfunction "+IN_12") (pintype "input"))
      (node (ref "R21") (pin "1") (pinfunction "1_1") (pintype "passive"))
    )
    (net (code "58") (name "Net-(IC2D--IN)") (class "Default")
      (node (ref "IC2") (pin "13") (pinfunction "-IN_13") (pintype "input"))
      (node (ref "R20") (pin "1") (pinfunction "1_1") (pintype "passive"))
      (node (ref "R22") (pin "1") (pinfunction "1_1") (pintype "passive"))
      (node (ref "R23") (pin "2") (pinfunction "2_2") (pintype "passive"))
    )
    (net (code "59") (name "Net-(IC3A--IN)") (class "Default")
      (node (ref "IC3") (pin "2") (pinfunction "-IN_2") (pintype "input"))
      (node (ref "R7") (pin "2") (pinfunction "2_2") (pintype "passive"))
      (node (ref "R8") (pin "2") (pinfunction "2_2") (pintype "passive"))
      (node (ref "R9") (pin "1") (pinfunction "1_1") (pintype "passive"))
    )
    (net (code "60") (name "Net-(IC3A-OUT)") (class "Default")
      (node (ref "IC3") (pin "1") (pinfunction "OUT_1") (pintype "output"))
      (node (ref "Q1") (pin "2") (pinfunction "B_2") (pintype "passive"))
      (node (ref "R9") (pin "2") (pinfunction "2_2") (pintype "passive"))
    )
    (net (code "61") (name "Net-(IC3B--IN)") (class "Default")
      (node (ref "C5") (pin "1") (pinfunction "1_1") (pintype "passive"))
      (node (ref "IC3") (pin "6") (pinfunction "-IN_6") (pintype "input"))
      (node (ref "Q1") (pin "1") (pinfunction "C_1") (pintype "passive"))
      (node (ref "R10") (pin "2") (pinfunction "2_2") (pintype "passive"))
    )
    (net (code "62") (name "Net-(IC3B-OUT)") (class "Default")
      (node (ref "C5") (pin "2") (pinfunction "2_2") (pintype "passive"))
      (node (ref "IC3") (pin "7") (pinfunction "OUT_7") (pintype "output"))
      (node (ref "R11") (pin "2") (pinfunction "2_2") (pintype "passive"))
    )
    (net (code "63") (name "Net-(IC3C--IN)") (class "Default")
      (node (ref "IC3") (pin "9") (pinfunction "-IN_9") (pintype "input"))
      (node (ref "R3") (pin "2") (pinfunction "2_2") (pintype "passive"))
      (node (ref "R4") (pin "2") (pinfunction "2_2") (pintype "passive"))
      (node (ref "R5") (pin "2") (pinfunction "2_2") (pintype "passive"))
      (node (ref "R6") (pin "1") (pinfunction "1_1") (pintype "passive"))
    )
    (net (code "64") (name "Net-(IC3C-OUT)") (class "Default")
      (node (ref "IC3") (pin "8") (pinfunction "OUT_8") (pintype "output"))
      (node (ref "R6") (pin "2") (pinfunction "2_2") (pintype "passive"))
      (node (ref "R7") (pin "1") (pinfunction "1_1") (pintype "passive"))
    )
    (net (code "65") (name "Net-(IC3D-+IN)") (class "Default")
      (node (ref "IC3") (pin "12") (pinfunction "+IN_12") (pintype "input"))
      (node (ref "R25") (pin "2") (pinfunction "2_2") (pintype "passive"))
      (node (ref "R26") (pin "2") (pinfunction "2_2") (pintype "passive"))
    )
    (net (code "66") (name "Net-(IC3D--IN)") (class "Default")
      (node (ref "IC3") (pin "13") (pinfunction "-IN_13") (pintype "input"))
      (node (ref "R24") (pin "2") (pinfunction "2_2") (pintype "passive"))
      (node (ref "R27") (pin "1") (pinfunction "1_1") (pintype "passive"))
    )
    (net (code "67") (name "Net-(IC4A--IN)") (class "Default")
      (node (ref "IC4") (pin "2") (pinfunction "-IN_2") (pintype "input"))
      (node (ref "R28") (pin "1") (pinfunction "1_1") (pintype "passive"))
      (node (ref "R29") (pin "1") (pinfunction "1_1") (pintype "passive"))
      (node (ref "R30") (pin "2") (pinfunction "2_2") (pintype "passive"))
    )
    (net (code "68") (name "Net-(IC4A-OUT)") (class "Default")
      (node (ref "IC4") (pin "1") (pinfunction "OUT_1") (pintype "output"))
      (node (ref "IC4") (pin "5") (pinfunction "+IN_5") (pintype "input"))
      (node (ref "R30") (pin "1") (pinfunction "1_1") (pintype "passive"))
    )
    (net (code "69") (name "Net-(IC4B--IN)") (class "Default")
      (node (ref "D3") (pin "C") (pinfunction "C_C") (pintype "passive"))
      (node (ref "IC4") (pin "6") (pinfunction "-IN_6") (pintype "input"))
      (node (ref "Q3") (pin "3") (pinfunction "E_3") (pintype "passive"))
      (node (ref "R31") (pin "2") (pinfunction "2_2") (pintype "passive"))
    )
    (net (code "70") (name "Net-(IC4B-OUT)") (class "Default")
      (node (ref "D3") (pin "A") (pinfunction "A_A") (pintype "passive"))
      (node (ref "IC4") (pin "7") (pinfunction "OUT_7") (pintype "output"))
      (node (ref "Q3") (pin "2") (pinfunction "B_2") (pintype "passive"))
    )
    (net (code "71") (name "Net-(IC4C-+IN)") (class "Default")
      (node (ref "IC4") (pin "10") (pinfunction "+IN_10") (pintype "input"))
      (node (ref "IC4") (pin "14") (pinfunction "OUT_14") (pintype "output"))
      (node (ref "R39") (pin "1") (pinfunction "1_1") (pintype "passive"))
    )
    (net (code "72") (name "Net-(IC4C--IN)") (class "Default")
      (node (ref "D4") (pin "C") (pinfunction "C_C") (pintype "passive"))
      (node (ref "IC4") (pin "9") (pinfunction "-IN_9") (pintype "input"))
      (node (ref "Q4") (pin "3") (pinfunction "E_3") (pintype "passive"))
      (node (ref "R40") (pin "2") (pinfunction "2_2") (pintype "passive"))
    )
    (net (code "73") (name "Net-(IC4C-OUT)") (class "Default")
      (node (ref "D4") (pin "A") (pinfunction "A_A") (pintype "passive"))
      (node (ref "IC4") (pin "8") (pinfunction "OUT_8") (pintype "output"))
      (node (ref "Q4") (pin "2") (pinfunction "B_2") (pintype "passive"))
    )
    (net (code "74") (name "Net-(IC4D--IN)") (class "Default")
      (node (ref "IC4") (pin "13") (pinfunction "-IN_13") (pintype "input"))
      (node (ref "R37") (pin "1") (pinfunction "1_1") (pintype "passive"))
      (node (ref "R38") (pin "1") (pinfunction "1_1") (pintype "passive"))
      (node (ref "R39") (pin "2") (pinfunction "2_2") (pintype "passive"))
    )
    (net (code "75") (name "Net-(IC5-Pad6)") (class "Default")
      (node (ref "IC5") (pin "6") (pinfunction "6_6") (pintype "bidirectional"))
      (node (ref "R46") (pin "1") (pinfunction "1_1") (pintype "passive"))
    )
    (net (code "76") (name "Net-(IC6A-B)") (class "Default")
      (node (ref "IC6") (pin "5") (pinfunction "OUT_5") (pintype "output"))
      (node (ref "IC6") (pin "7") (pinfunction "B_7") (pintype "passive"))
      (node (ref "R34") (pin "1") (pinfunction "1_1") (pintype "passive"))
      (node (ref "R35") (pin "2") (pinfunction "2_2") (pintype "passive"))
    )
    (net (code "77") (name "Net-(IC6B-B)") (class "Default")
      (node (ref "IC6") (pin "10") (pinfunction "B_10") (pintype "passive"))
      (node (ref "IC6") (pin "12") (pinfunction "OUT_12") (pintype "output"))
      (node (ref "R43") (pin "1") (pinfunction "1_1") (pintype "passive"))
      (node (ref "R44") (pin "2") (pinfunction "2_2") (pintype "passive"))
    )
    (net (code "78") (name "Net-(IC6C-IN_P)") (class "Default")
      (node (ref "IC6") (pin "3") (pinfunction "IN_P_3") (pintype "input"))
      (node (ref "R32") (pin "1") (pinfunction "1_1") (pintype "passive"))
      (node (ref "R33") (pin "2") (pinfunction "2_2") (pintype "passive"))
    )
    (net (code "79") (name "Net-(IC6C-I_BIAS)") (class "Default")
      (node (ref "IC6") (pin "1") (pinfunction "I_BIAS_1") (pintype "input"))
      (node (ref "Q3") (pin "1") (pinfunction "C_1") (pintype "passive"))
    )
    (net (code "80") (name "Net-(IC6D-IN_P)") (class "Default")
      (node (ref "IC6") (pin "14") (pinfunction "IN_P_14") (pintype "input"))
      (node (ref "R41") (pin "1") (pinfunction "1_1") (pintype "passive"))
      (node (ref "R42") (pin "2") (pinfunction "2_2") (pintype "passive"))
    )
    (net (code "81") (name "Net-(IC6D-I_BIAS)") (class "Default")
      (node (ref "IC6") (pin "16") (pinfunction "I_BIAS_16") (pintype "input"))
      (node (ref "Q4") (pin "1") (pinfunction "C_1") (pintype "passive"))
    )
    (net (code "82") (name "Net-(Q1-E)") (class "Default")
      (node (ref "Q1") (pin "3") (pinfunction "E_3") (pintype "passive"))
      (node (ref "Q2") (pin "3") (pinfunction "E_3") (pintype "passive"))
      (node (ref "R11") (pin "1") (pinfunction "1_1") (pintype "passive"))
    )
    (net (code "83") (name "Net-(X2A-KL)") (class "Default")
      (node (ref "D2") (pin "C") (pinfunction "C_C") (pintype "passive"))
      (node (ref "X2") (pin "1") (pinfunction "KL_1") (pintype "passive"))
      (node (ref "X2") (pin "2") (pinfunction "KL_2") (pintype "passive"))
    )
    (net (code "84") (name "Net-(X2B-KL)") (class "Default")
      (node (ref "D1") (pin "A") (pinfunction "A_A") (pintype "passive"))
      (node (ref "X2") (pin "10") (pinfunction "KL_10") (pintype "passive"))
      (node (ref "X2") (pin "9") (pinfunction "KL_9") (pintype "passive"))
    )
    (net (code "85") (name "unconnected-(IC5-Pad5)") (class "Default")
      (node (ref "IC5") (pin "5") (pinfunction "5_5") (pintype "bidirectional"))
    )
    (net (code "86") (name "unconnected-(IC6C-I_DIODE-Pad2)") (class "Default")
      (node (ref "IC6") (pin "2") (pinfunction "I_DIODE_2") (pintype "input"))
    )
    (net (code "87") (name "unconnected-(IC6D-I_DIODE-Pad15)") (class "Default")
      (node (ref "IC6") (pin "15") (pinfunction "I_DIODE_15") (pintype "input"))
    )
    (net (code "88") (name "unconnected-(JP1-Pad8)") (class "Default")
      (node (ref "JP1") (pin "8") (pinfunction "8_8") (pintype "passive"))
    )
    (net (code "89") (name "unconnected-(JP1-Pad10)") (class "Default")
      (node (ref "JP1") (pin "10") (pinfunction "10_10") (pintype "passive"))
    )
    (net (code "90") (name "unconnected-(JP1-Pad12)") (class "Default")
      (node (ref "JP1") (pin "12") (pinfunction "12_12") (pintype "passive"))
    )
    (net (code "91") (name "unconnected-(JP1-Pad13)") (class "Default")
      (node (ref "JP1") (pin "13") (pinfunction "13_13") (pintype "passive"))
    )
    (net (code "92") (name "unconnected-(JP1-Pad14)") (class "Default")
      (node (ref "JP1") (pin "14") (pinfunction "14_14") (pintype "passive"))
    )
    (net (code "93") (name "unconnected-(JP1-Pad16)") (class "Default")
      (node (ref "JP1") (pin "16") (pinfunction "16_16") (pintype "passive"))
    )
    (net (code "94") (name "unconnected-(JP1-Pad18)") (class "Default")
      (node (ref "JP1") (pin "18") (pinfunction "18_18") (pintype "passive"))
    )
    (net (code "95") (name "unconnected-(JP2-Pad4)") (class "Default")
      (node (ref "JP2") (pin "4") (pinfunction "4_4") (pintype "passive"))
    )
    (net (code "96") (name "unconnected-(JP2-Pad6)") (class "Default")
      (node (ref "JP2") (pin "6") (pinfunction "6_6") (pintype "passive"))
    )
    (net (code "97") (name "unconnected-(JP2-Pad8)") (class "Default")
      (node (ref "JP2") (pin "8") (pinfunction "8_8") (pintype "passive"))
    )
    (net (code "98") (name "unconnected-(JP2-Pad10)") (class "Default")
      (node (ref "JP2") (pin "10") (pinfunction "10_10") (pintype "passive"))
    )
    (net (code "99") (name "unconnected-(JP2-Pad14)") (class "Default")
      (node (ref "JP2") (pin "14") (pinfunction "14_14") (pintype "passive"))
    )
    (net (code "100") (name "unconnected-(JP2-Pad17)") (class "Default")
      (node (ref "JP2") (pin "17") (pinfunction "17_17") (pintype "passive"))
    )
  )
)
